# 7_connectors.net
KiCad netlist of a schematic drawn in Altium Designer
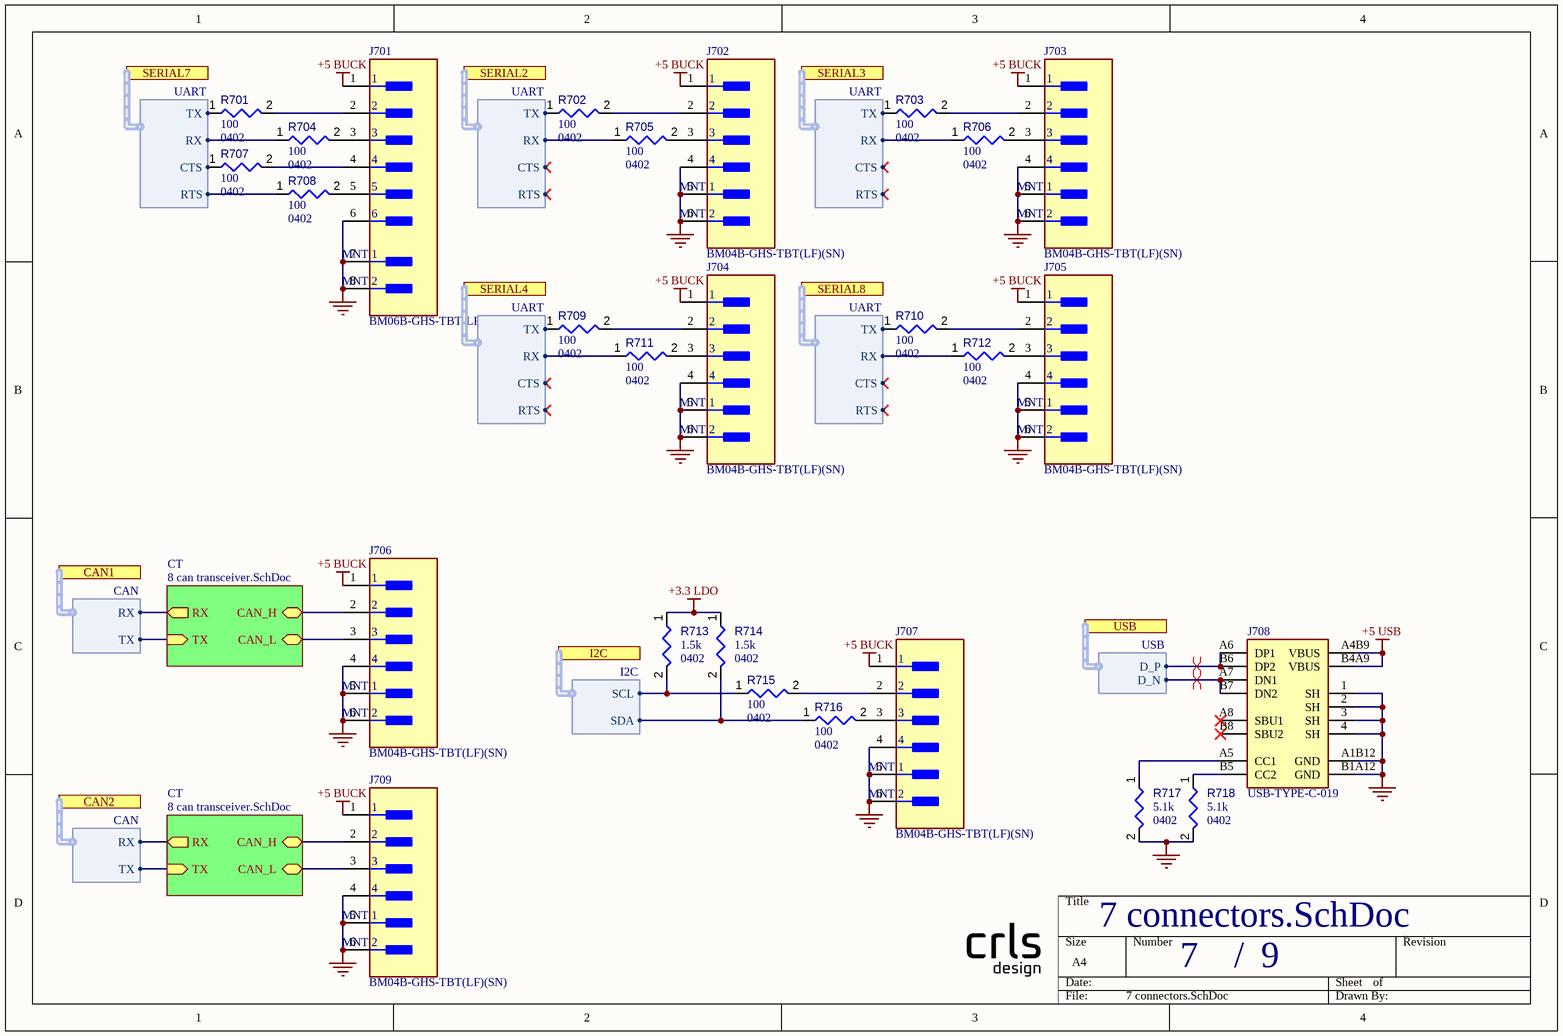
[diagram p0: 7 connectors.SchDoc]

(export (version "E")
  (design (tool "Eeschema 10.0.6"))
  (components
    (comp (ref "J701")
      (value "BM06B-GHS-TBT(LF)(SN)")
      (footprint "FP-BM06B-GHS-TBT_LF_SN-MFG")
      (description "CONN HEADER SMD 6POS 1.25MM")
      (libsource (lib "Altium Content Vault") (part "ed24c53d9ba001d1a2a686240a95171"))
    )
    (comp (ref "J702")
      (value "BM04B-GHS-TBT(LF)(SN)")
      (footprint "FP-BM04B-GHS-TBT_LF_SN-MFG")
      (description "CONN HEADER SMD 4POS 1.25MM")
      (libsource (lib "Altium Content Vault") (part "8e3688c4b118bffc0dd9b7401e414ba"))
    )
    (comp (ref "J703")
      (value "BM04B-GHS-TBT(LF)(SN)")
      (footprint "FP-BM04B-GHS-TBT_LF_SN-MFG")
      (description "CONN HEADER SMD 4POS 1.25MM")
      (libsource (lib "Altium Content Vault") (part "8e3688c4b118bffc0dd9b7401e414ba"))
    )
    (comp (ref "J704")
      (value "BM04B-GHS-TBT(LF)(SN)")
      (footprint "FP-BM04B-GHS-TBT_LF_SN-MFG")
      (description "CONN HEADER SMD 4POS 1.25MM")
      (libsource (lib "Altium Content Vault") (part "8e3688c4b118bffc0dd9b7401e414ba"))
    )
    (comp (ref "J705")
      (value "BM04B-GHS-TBT(LF)(SN)")
      (footprint "FP-BM04B-GHS-TBT_LF_SN-MFG")
      (description "CONN HEADER SMD 4POS 1.25MM")
      (libsource (lib "Altium Content Vault") (part "8e3688c4b118bffc0dd9b7401e414ba"))
    )
    (comp (ref "J706")
      (value "BM04B-GHS-TBT(LF)(SN)")
      (footprint "FP-BM04B-GHS-TBT_LF_SN-MFG")
      (description "CONN HEADER SMD 4POS 1.25MM")
      (libsource (lib "Altium Content Vault") (part "8e3688c4b118bffc0dd9b7401e414ba"))
    )
    (comp (ref "J707")
      (value "BM04B-GHS-TBT(LF)(SN)")
      (footprint "FP-BM04B-GHS-TBT_LF_SN-MFG")
      (description "CONN HEADER SMD 4POS 1.25MM")
      (libsource (lib "Altium Content Vault") (part "8e3688c4b118bffc0dd9b7401e414ba"))
    )
    (comp (ref "J708")
      (value "USB-TYPE-C-019")
      (footprint "USB-TYPE-C-12+4P")
      (fields (field (name "MANUFACTURER") "DEALON(德艺隆)"))
      (libsource (lib "JLCPCB Library") (part "USB-TYPE-C-019"))
    )
    (comp (ref "J709")
      (value "BM04B-GHS-TBT(LF)(SN)")
      (footprint "FP-BM04B-GHS-TBT_LF_SN-MFG")
      (description "CONN HEADER SMD 4POS 1.25MM")
      (libsource (lib "Altium Content Vault") (part "8e3688c4b118bffc0dd9b7401e414ba"))
    )
    (comp (ref "R701")
      (value "100")
      (footprint "RESC0402(1005)_L")
      (description "Resistor")
      (fields
        (field (name "CASE/PACKAGE") "0402")
        (field (name "TOLERANCE") "1%")
        (field (name "Comment") "Resistors,0402,1%,100")
      )
      (libsource (lib "UBC Uncrewed Aircraft Systems") (part "RES-2"))
    )
    (comp (ref "R702")
      (value "100")
      (footprint "RESC0402(1005)_L")
      (description "Resistor")
      (fields
        (field (name "CASE/PACKAGE") "0402")
        (field (name "TOLERANCE") "1%")
        (field (name "Comment") "Resistors,0402,1%,100")
      )
      (libsource (lib "UBC Uncrewed Aircraft Systems") (part "RES-2"))
    )
    (comp (ref "R703")
      (value "100")
      (footprint "RESC0402(1005)_L")
      (description "Resistor")
      (fields
        (field (name "CASE/PACKAGE") "0402")
        (field (name "TOLERANCE") "1%")
        (field (name "Comment") "Resistors,0402,1%,100")
      )
      (libsource (lib "UBC Uncrewed Aircraft Systems") (part "RES-2"))
    )
    (comp (ref "R704")
      (value "100")
      (footprint "RESC0402(1005)_L")
      (description "Resistor")
      (fields
        (field (name "CASE/PACKAGE") "0402")
        (field (name "TOLERANCE") "1%")
        (field (name "Comment") "Resistors,0402,1%,100")
      )
      (libsource (lib "UBC Uncrewed Aircraft Systems") (part "RES-2"))
    )
    (comp (ref "R705")
      (value "100")
      (footprint "RESC0402(1005)_L")
      (description "Resistor")
      (fields
        (field (name "CASE/PACKAGE") "0402")
        (field (name "TOLERANCE") "1%")
        (field (name "Comment") "Resistors,0402,1%,100")
      )
      (libsource (lib "UBC Uncrewed Aircraft Systems") (part "RES-2"))
    )
    (comp (ref "R706")
      (value "100")
      (footprint "RESC0402(1005)_L")
      (description "Resistor")
      (fields
        (field (name "CASE/PACKAGE") "0402")
        (field (name "TOLERANCE") "1%")
        (field (name "Comment") "Resistors,0402,1%,100")
      )
      (libsource (lib "UBC Uncrewed Aircraft Systems") (part "RES-2"))
    )
    (comp (ref "R707")
      (value "100")
      (footprint "RESC0402(1005)_L")
      (description "Resistor")
      (fields
        (field (name "CASE/PACKAGE") "0402")
        (field (name "TOLERANCE") "1%")
        (field (name "Comment") "Resistors,0402,1%,100")
      )
      (libsource (lib "UBC Uncrewed Aircraft Systems") (part "RES-2"))
    )
    (comp (ref "R708")
      (value "100")
      (footprint "RESC0402(1005)_L")
      (description "Resistor")
      (fields
        (field (name "CASE/PACKAGE") "0402")
        (field (name "TOLERANCE") "1%")
        (field (name "Comment") "Resistors,0402,1%,100")
      )
      (libsource (lib "UBC Uncrewed Aircraft Systems") (part "RES-2"))
    )
    (comp (ref "R709")
      (value "100")
      (footprint "RESC0402(1005)_L")
      (description "Resistor")
      (fields
        (field (name "CASE/PACKAGE") "0402")
        (field (name "TOLERANCE") "1%")
        (field (name "Comment") "Resistors,0402,1%,100")
      )
      (libsource (lib "UBC Uncrewed Aircraft Systems") (part "RES-2"))
    )
    (comp (ref "R710")
      (value "100")
      (footprint "RESC0402(1005)_L")
      (description "Resistor")
      (fields
        (field (name "CASE/PACKAGE") "0402")
        (field (name "TOLERANCE") "1%")
        (field (name "Comment") "Resistors,0402,1%,100")
      )
      (libsource (lib "UBC Uncrewed Aircraft Systems") (part "RES-2"))
    )
    (comp (ref "R711")
      (value "100")
      (footprint "RESC0402(1005)_L")
      (description "Resistor")
      (fields
        (field (name "CASE/PACKAGE") "0402")
        (field (name "TOLERANCE") "1%")
        (field (name "Comment") "Resistors,0402,1%,100")
      )
      (libsource (lib "UBC Uncrewed Aircraft Systems") (part "RES-2"))
    )
    (comp (ref "R712")
      (value "100")
      (footprint "RESC0402(1005)_L")
      (description "Resistor")
      (fields
        (field (name "CASE/PACKAGE") "0402")
        (field (name "TOLERANCE") "1%")
        (field (name "Comment") "Resistors,0402,1%,100")
      )
      (libsource (lib "UBC Uncrewed Aircraft Systems") (part "RES-2"))
    )
    (comp (ref "R713")
      (value "1.5k")
      (footprint "RESC0402(1005)_L")
      (description "Resistor")
      (fields
        (field (name "CASE/PACKAGE") "0402")
        (field (name "TOLERANCE") "1%")
        (field (name "Comment") "Resistors,0402,1%,1.5k")
      )
      (libsource (lib "UBC Uncrewed Aircraft Systems") (part "RES-2"))
    )
    (comp (ref "R714")
      (value "1.5k")
      (footprint "RESC0402(1005)_L")
      (description "Resistor")
      (fields
        (field (name "CASE/PACKAGE") "0402")
        (field (name "TOLERANCE") "1%")
        (field (name "Comment") "Resistors,0402,1%,1.5k")
      )
      (libsource (lib "UBC Uncrewed Aircraft Systems") (part "RES-2"))
    )
    (comp (ref "R715")
      (value "100")
      (footprint "RESC0402(1005)_L")
      (description "Resistor")
      (fields
        (field (name "CASE/PACKAGE") "0402")
        (field (name "TOLERANCE") "1%")
        (field (name "Comment") "Resistors,0402,1%,100")
      )
      (libsource (lib "UBC Uncrewed Aircraft Systems") (part "RES-2"))
    )
    (comp (ref "R716")
      (value "100")
      (footprint "RESC0402(1005)_L")
      (description "Resistor")
      (fields
        (field (name "CASE/PACKAGE") "0402")
        (field (name "TOLERANCE") "1%")
        (field (name "Comment") "Resistors,0402,1%,100")
      )
      (libsource (lib "UBC Uncrewed Aircraft Systems") (part "RES-2"))
    )
    (comp (ref "R717")
      (value "5.1k")
      (footprint "RESC0402(1005)_L")
      (description "Resistor")
      (fields
        (field (name "CASE/PACKAGE") "0402")
        (field (name "TOLERANCE") "1%")
        (field (name "Comment") "Resistors,0402,1%,5.1k")
      )
      (libsource (lib "UBC Uncrewed Aircraft Systems") (part "RES-2"))
    )
    (comp (ref "R718")
      (value "5.1k")
      (footprint "RESC0402(1005)_L")
      (description "Resistor")
      (fields
        (field (name "CASE/PACKAGE") "0402")
        (field (name "TOLERANCE") "1%")
        (field (name "Comment") "Resistors,0402,1%,5.1k")
      )
      (libsource (lib "UBC Uncrewed Aircraft Systems") (part "RES-2"))
    )
  )
  (nets
    (net (code "5") (name "+3.3 LDO") (class "Default")
      (node (ref "R713") (pin "1") (pinfunction "1_1") (pintype "passive"))
      (node (ref "R714") (pin "1") (pinfunction "1_1") (pintype "passive"))
    )
    (net (code "6") (name "+5 BUCK") (class "Default")
      (node (ref "J701") (pin "1") (pinfunction "1_1") (pintype "passive"))
      (node (ref "J702") (pin "1") (pinfunction "1_1") (pintype "passive"))
      (node (ref "J703") (pin "1") (pinfunction "1_1") (pintype "passive"))
      (node (ref "J704") (pin "1") (pinfunction "1_1") (pintype "passive"))
      (node (ref "J705") (pin "1") (pinfunction "1_1") (pintype "passive"))
      (node (ref "J706") (pin "1") (pinfunction "1_1") (pintype "passive"))
      (node (ref "J707") (pin "1") (pinfunction "1_1") (pintype "passive"))
      (node (ref "J709") (pin "1") (pinfunction "1_1") (pintype "passive"))
    )
    (net (code "7") (name "+5 USB") (class "Default")
      (node (ref "J708") (pin "A4B9") (pinfunction "VBUS_A4B9") (pintype "power_in"))
      (node (ref "J708") (pin "B4A9") (pinfunction "VBUS_B4A9") (pintype "power_in"))
    )
    (net (code "8") (name "/CAN_H") (class "Default")
      (node (ref "J706") (pin "2") (pinfunction "2_2") (pintype "passive"))
    )
    (net (code "9") (name "/CAN_H_1") (class "Default")
      (node (ref "J709") (pin "2") (pinfunction "2_2") (pintype "passive"))
    )
    (net (code "10") (name "/CAN_L") (class "Default")
      (node (ref "J706") (pin "3") (pinfunction "3_3") (pintype "passive"))
    )
    (net (code "11") (name "/CAN_L_1") (class "Default")
      (node (ref "J709") (pin "3") (pinfunction "3_3") (pintype "passive"))
    )
    (net (code "12") (name "/D_N") (class "Default")
      (node (ref "J708") (pin "A7") (pinfunction "DN1_A7") (pintype "passive"))
      (node (ref "J708") (pin "B7") (pinfunction "DN2_B7") (pintype "passive"))
    )
    (net (code "13") (name "/D_P") (class "Default")
      (node (ref "J708") (pin "A6") (pinfunction "DP1_A6") (pintype "passive"))
      (node (ref "J708") (pin "B6") (pinfunction "DP2_B6") (pintype "passive"))
    )
    (net (code "16") (name "/SCL") (class "Default")
      (node (ref "R713") (pin "2") (pinfunction "2_2") (pintype "passive"))
      (node (ref "R715") (pin "1") (pinfunction "1_1") (pintype "passive"))
    )
    (net (code "17") (name "/SDA") (class "Default")
      (node (ref "R714") (pin "2") (pinfunction "2_2") (pintype "passive"))
      (node (ref "R716") (pin "1") (pinfunction "1_1") (pintype "passive"))
    )
    (net (code "24") (name "GND") (class "Default")
      (node (ref "J701") (pin "6") (pinfunction "6_6") (pintype "passive"))
      (node (ref "J701") (pin "7") (pinfunction "MNT_1_7") (pintype "passive"))
      (node (ref "J701") (pin "8") (pinfunction "MNT_2_8") (pintype "passive"))
      (node (ref "J702") (pin "4") (pinfunction "4_4") (pintype "passive"))
      (node (ref "J702") (pin "5") (pinfunction "MNT_1_5") (pintype "passive"))
      (node (ref "J702") (pin "6") (pinfunction "MNT_2_6") (pintype "passive"))
      (node (ref "J703") (pin "4") (pinfunction "4_4") (pintype "passive"))
      (node (ref "J703") (pin "5") (pinfunction "MNT_1_5") (pintype "passive"))
      (node (ref "J703") (pin "6") (pinfunction "MNT_2_6") (pintype "passive"))
      (node (ref "J704") (pin "4") (pinfunction "4_4") (pintype "passive"))
      (node (ref "J704") (pin "5") (pinfunction "MNT_1_5") (pintype "passive"))
      (node (ref "J704") (pin "6") (pinfunction "MNT_2_6") (pintype "passive"))
      (node (ref "J705") (pin "4") (pinfunction "4_4") (pintype "passive"))
      (node (ref "J705") (pin "5") (pinfunction "MNT_1_5") (pintype "passive"))
      (node (ref "J705") (pin "6") (pinfunction "MNT_2_6") (pintype "passive"))
      (node (ref "J706") (pin "4") (pinfunction "4_4") (pintype "passive"))
      (node (ref "J706") (pin "5") (pinfunction "MNT_1_5") (pintype "passive"))
      (node (ref "J706") (pin "6") (pinfunction "MNT_2_6") (pintype "passive"))
      (node (ref "J707") (pin "4") (pinfunction "4_4") (pintype "passive"))
      (node (ref "J707") (pin "5") (pinfunction "MNT_1_5") (pintype "passive"))
      (node (ref "J707") (pin "6") (pinfunction "MNT_2_6") (pintype "passive"))
      (node (ref "J708") (pin "1") (pinfunction "SH_1") (pintype "passive"))
      (node (ref "J708") (pin "2") (pinfunction "SH_2") (pintype "passive"))
      (node (ref "J708") (pin "3") (pinfunction "SH_3") (pintype "passive"))
      (node (ref "J708") (pin "4") (pinfunction "SH_4") (pintype "passive"))
      (node (ref "J708") (pin "A1B12") (pinfunction "GND_A1B12") (pintype "power_in"))
      (node (ref "J708") (pin "B1A12") (pinfunction "GND_B1A12") (pintype "power_in"))
      (node (ref "J709") (pin "4") (pinfunction "4_4") (pintype "passive"))
      (node (ref "J709") (pin "5") (pinfunction "MNT_1_5") (pintype "passive"))
      (node (ref "J709") (pin "6") (pinfunction "MNT_2_6") (pintype "passive"))
      (node (ref "R717") (pin "2") (pinfunction "2_2") (pintype "passive"))
      (node (ref "R718") (pin "2") (pinfunction "2_2") (pintype "passive"))
    )
    (net (code "25") (name "Net-(J701-Pad2)") (class "Default")
      (node (ref "J701") (pin "2") (pinfunction "2_2") (pintype "passive"))
      (node (ref "R701") (pin "2") (pinfunction "2_2") (pintype "passive"))
    )
    (net (code "26") (name "Net-(J701-Pad3)") (class "Default")
      (node (ref "J701") (pin "3") (pinfunction "3_3") (pintype "passive"))
      (node (ref "R704") (pin "2") (pinfunction "2_2") (pintype "passive"))
    )
    (net (code "27") (name "Net-(J701-Pad4)") (class "Default")
      (node (ref "J701") (pin "4") (pinfunction "4_4") (pintype "passive"))
      (node (ref "R707") (pin "2") (pinfunction "2_2") (pintype "passive"))
    )
    (net (code "28") (name "Net-(J701-Pad5)") (class "Default")
      (node (ref "J701") (pin "5") (pinfunction "5_5") (pintype "passive"))
      (node (ref "R708") (pin "2") (pinfunction "2_2") (pintype "passive"))
    )
    (net (code "29") (name "Net-(J702-Pad2)") (class "Default")
      (node (ref "J702") (pin "2") (pinfunction "2_2") (pintype "passive"))
      (node (ref "R702") (pin "2") (pinfunction "2_2") (pintype "passive"))
    )
    (net (code "30") (name "Net-(J702-Pad3)") (class "Default")
      (node (ref "J702") (pin "3") (pinfunction "3_3") (pintype "passive"))
      (node (ref "R705") (pin "2") (pinfunction "2_2") (pintype "passive"))
    )
    (net (code "31") (name "Net-(J703-Pad2)") (class "Default")
      (node (ref "J703") (pin "2") (pinfunction "2_2") (pintype "passive"))
      (node (ref "R703") (pin "2") (pinfunction "2_2") (pintype "passive"))
    )
    (net (code "32") (name "Net-(J703-Pad3)") (class "Default")
      (node (ref "J703") (pin "3") (pinfunction "3_3") (pintype "passive"))
      (node (ref "R706") (pin "2") (pinfunction "2_2") (pintype "passive"))
    )
    (net (code "33") (name "Net-(J704-Pad2)") (class "Default")
      (node (ref "J704") (pin "2") (pinfunction "2_2") (pintype "passive"))
      (node (ref "R709") (pin "2") (pinfunction "2_2") (pintype "passive"))
    )
    (net (code "34") (name "Net-(J704-Pad3)") (class "Default")
      (node (ref "J704") (pin "3") (pinfunction "3_3") (pintype "passive"))
      (node (ref "R711") (pin "2") (pinfunction "2_2") (pintype "passive"))
    )
    (net (code "35") (name "Net-(J705-Pad2)") (class "Default")
      (node (ref "J705") (pin "2") (pinfunction "2_2") (pintype "passive"))
      (node (ref "R710") (pin "2") (pinfunction "2_2") (pintype "passive"))
    )
    (net (code "36") (name "Net-(J705-Pad3)") (class "Default")
      (node (ref "J705") (pin "3") (pinfunction "3_3") (pintype "passive"))
      (node (ref "R712") (pin "2") (pinfunction "2_2") (pintype "passive"))
    )
    (net (code "37") (name "Net-(J707-Pad2)") (class "Default")
      (node (ref "J707") (pin "2") (pinfunction "2_2") (pintype "passive"))
      (node (ref "R715") (pin "2") (pinfunction "2_2") (pintype "passive"))
    )
    (net (code "38") (name "Net-(J707-Pad3)") (class "Default")
      (node (ref "J707") (pin "3") (pinfunction "3_3") (pintype "passive"))
      (node (ref "R716") (pin "2") (pinfunction "2_2") (pintype "passive"))
    )
    (net (code "39") (name "Net-(J708-CC1)") (class "Default")
      (node (ref "J708") (pin "A5") (pinfunction "CC1_A5") (pintype "passive"))
      (node (ref "R717") (pin "1") (pinfunction "1_1") (pintype "passive"))
    )
    (net (code "40") (name "Net-(J708-CC2)") (class "Default")
      (node (ref "J708") (pin "B5") (pinfunction "CC2_B5") (pintype "passive"))
      (node (ref "R718") (pin "1") (pinfunction "1_1") (pintype "passive"))
    )
    (net (code "41") (name "unconnected-(J708-SBU1-PadA8)") (class "Default")
      (node (ref "J708") (pin "A8") (pinfunction "SBU1_A8") (pintype "passive+no_connect"))
    )
    (net (code "42") (name "unconnected-(J708-SBU2-PadB8)") (class "Default")
      (node (ref "J708") (pin "B8") (pinfunction "SBU2_B8") (pintype "passive+no_connect"))
    )
    (net (code "43") (name "unconnected-(R701-Pad1)") (class "Default")
      (node (ref "R701") (pin "1") (pinfunction "1_1") (pintype "passive"))
    )
    (net (code "44") (name "unconnected-(R702-Pad1)") (class "Default")
      (node (ref "R702") (pin "1") (pinfunction "1_1") (pintype "passive"))
    )
    (net (code "45") (name "unconnected-(R703-Pad1)") (class "Default")
      (node (ref "R703") (pin "1") (pinfunction "1_1") (pintype "passive"))
    )
    (net (code "46") (name "unconnected-(R704-Pad1)") (class "Default")
      (node (ref "R704") (pin "1") (pinfunction "1_1") (pintype "passive"))
    )
    (net (code "47") (name "unconnected-(R705-Pad1)") (class "Default")
      (node (ref "R705") (pin "1") (pinfunction "1_1") (pintype "passive"))
    )
    (net (code "48") (name "unconnected-(R706-Pad1)") (class "Default")
      (node (ref "R706") (pin "1") (pinfunction "1_1") (pintype "passive"))
    )
    (net (code "49") (name "unconnected-(R707-Pad1)") (class "Default")
      (node (ref "R707") (pin "1") (pinfunction "1_1") (pintype "passive"))
    )
    (net (code "50") (name "unconnected-(R708-Pad1)") (class "Default")
      (node (ref "R708") (pin "1") (pinfunction "1_1") (pintype "passive"))
    )
    (net (code "51") (name "unconnected-(R709-Pad1)") (class "Default")
      (node (ref "R709") (pin "1") (pinfunction "1_1") (pintype "passive"))
    )
    (net (code "52") (name "unconnected-(R710-Pad1)") (class "Default")
      (node (ref "R710") (pin "1") (pinfunction "1_1") (pintype "passive"))
    )
    (net (code "53") (name "unconnected-(R711-Pad1)") (class "Default")
      (node (ref "R711") (pin "1") (pinfunction "1_1") (pintype "passive"))
    )
    (net (code "54") (name "unconnected-(R712-Pad1)") (class "Default")
      (node (ref "R712") (pin "1") (pinfunction "1_1") (pintype "passive"))
    )
  )
)
